# ledstripschematic.net
KiCad netlist of a schematic drawn in EasyEDA
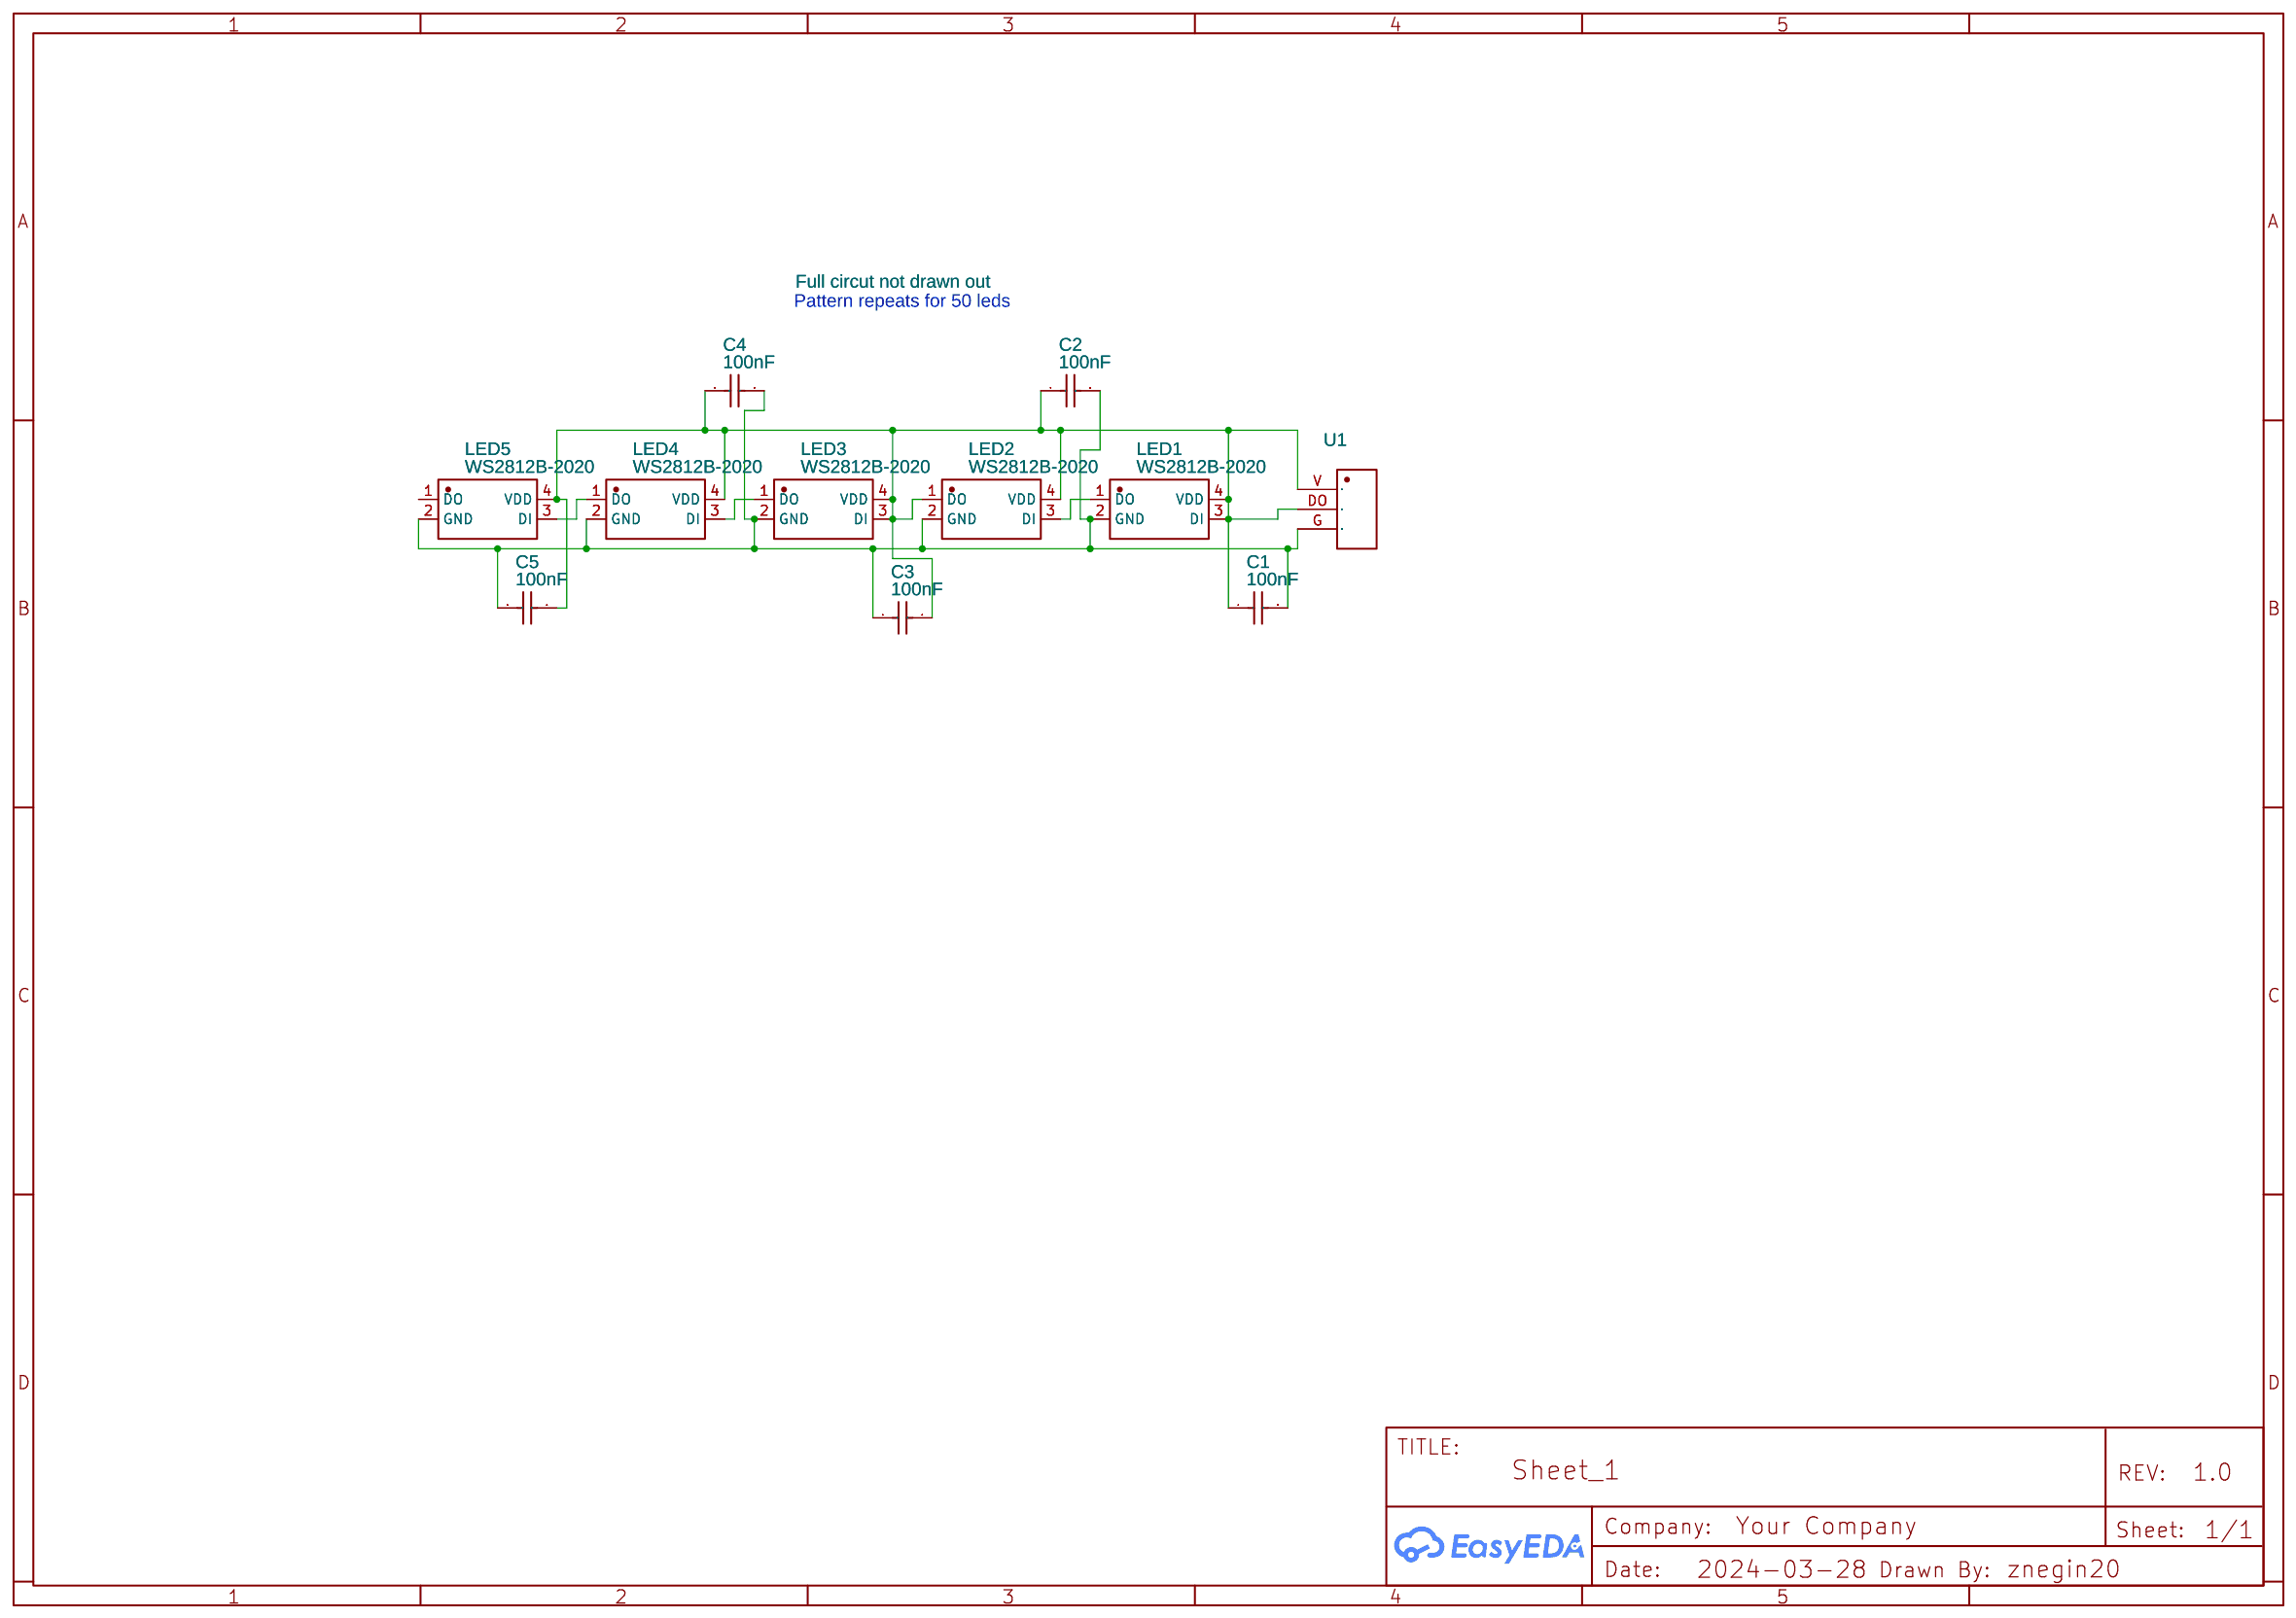
[diagram p0: schematic sheet]

(export (version "E")
  (design (tool "Eeschema 10.0.6"))
  (components
    (comp (ref "C1")
      (value "100nF")
      (fields
        (field (name "Manufacturer Part") "CL05B104KO5NNNC")
        (field (name "Manufacturer") "SAMSUNG(三星)")
      )
      (libsource (lib "") (part "CL05B104KO5NNNC"))
    )
    (comp (ref "C2")
      (value "100nF")
      (fields
        (field (name "Manufacturer Part") "CL05B104KO5NNNC")
        (field (name "Manufacturer") "SAMSUNG(三星)")
      )
      (libsource (lib "") (part "CL05B104KO5NNNC"))
    )
    (comp (ref "C3")
      (value "100nF")
      (fields
        (field (name "Manufacturer Part") "CL05B104KO5NNNC")
        (field (name "Manufacturer") "SAMSUNG(三星)")
      )
      (libsource (lib "") (part "CL05B104KO5NNNC"))
    )
    (comp (ref "C4")
      (value "100nF")
      (fields
        (field (name "Manufacturer Part") "CL05B104KO5NNNC")
        (field (name "Manufacturer") "SAMSUNG(三星)")
      )
      (libsource (lib "") (part "CL05B104KO5NNNC"))
    )
    (comp (ref "C5")
      (value "100nF")
      (fields
        (field (name "Manufacturer Part") "CL05B104KO5NNNC")
        (field (name "Manufacturer") "SAMSUNG(三星)")
      )
      (libsource (lib "") (part "CL05B104KO5NNNC"))
    )
    (comp (ref "LED1")
      (value "WS2812B-2020")
      (fields (field (name "Manufacturer") "worldsemi"))
      (libsource (lib "") (part "WS2812B-2020"))
    )
    (comp (ref "LED2")
      (value "WS2812B-2020")
      (fields (field (name "Manufacturer") "worldsemi"))
      (libsource (lib "") (part "WS2812B-2020"))
    )
    (comp (ref "LED3")
      (value "WS2812B-2020")
      (fields (field (name "Manufacturer") "worldsemi"))
      (libsource (lib "") (part "WS2812B-2020"))
    )
    (comp (ref "LED4")
      (value "WS2812B-2020")
      (fields (field (name "Manufacturer") "worldsemi"))
      (libsource (lib "") (part "WS2812B-2020"))
    )
    (comp (ref "LED5")
      (value "WS2812B-2020")
      (fields (field (name "Manufacturer") "worldsemi"))
      (libsource (lib "") (part "WS2812B-2020"))
    )
    (comp (ref "U1")
      (value "Full circut not drawn out")
      (fields (field (name "Manufacturer Part") "A2-3PA-2.54DSA(71)") (field (name "Manufacturer") "HRS(广濑)"))
      (libsource (lib "") (part "A2-3PA-2.54DSA(71)"))
    )
  )
  (nets
    (net (code "1") (name "Net-(LED1-DI)") (class "Default")
      (node (ref "C1") (pin "1") (pinfunction "1_1") (pintype "input"))
      (node (ref "C2") (pin "1") (pinfunction "1_1") (pintype "input"))
      (node (ref "C3") (pin "2") (pinfunction "2_2") (pintype "input"))
      (node (ref "C4") (pin "1") (pinfunction "1_1") (pintype "input"))
      (node (ref "C5") (pin "2") (pinfunction "2_2") (pintype "input"))
      (node (ref "LED1") (pin "3") (pinfunction "DI_3") (pintype "unspecified"))
      (node (ref "LED1") (pin "4") (pinfunction "VDD_4") (pintype "unspecified"))
      (node (ref "LED2") (pin "1") (pinfunction "DO_1") (pintype "unspecified"))
      (node (ref "LED2") (pin "4") (pinfunction "VDD_4") (pintype "unspecified"))
      (node (ref "LED3") (pin "3") (pinfunction "DI_3") (pintype "unspecified"))
      (node (ref "LED3") (pin "4") (pinfunction "VDD_4") (pintype "unspecified"))
      (node (ref "LED4") (pin "4") (pinfunction "VDD_4") (pintype "unspecified"))
      (node (ref "LED5") (pin "4") (pinfunction "VDD_4") (pintype "unspecified"))
      (node (ref "U1") (pin "DO") (pinfunction "2_DO") (pintype "unspecified"))
      (node (ref "U1") (pin "V") (pinfunction "1_V") (pintype "unspecified"))
    )
    (net (code "2") (name "Net-(LED1-DO)") (class "Default")
      (node (ref "LED1") (pin "1") (pinfunction "DO_1") (pintype "unspecified"))
      (node (ref "LED2") (pin "3") (pinfunction "DI_3") (pintype "unspecified"))
    )
    (net (code "3") (name "Net-(LED1-GND)") (class "Default")
      (node (ref "C1") (pin "2") (pinfunction "2_2") (pintype "input"))
      (node (ref "C2") (pin "2") (pinfunction "2_2") (pintype "input"))
      (node (ref "C3") (pin "1") (pinfunction "1_1") (pintype "input"))
      (node (ref "C4") (pin "2") (pinfunction "2_2") (pintype "input"))
      (node (ref "C5") (pin "1") (pinfunction "1_1") (pintype "input"))
      (node (ref "LED1") (pin "2") (pinfunction "GND_2") (pintype "unspecified"))
      (node (ref "LED2") (pin "2") (pinfunction "GND_2") (pintype "unspecified"))
      (node (ref "LED3") (pin "2") (pinfunction "GND_2") (pintype "unspecified"))
      (node (ref "LED4") (pin "2") (pinfunction "GND_2") (pintype "unspecified"))
      (node (ref "LED5") (pin "2") (pinfunction "GND_2") (pintype "unspecified"))
      (node (ref "U1") (pin "G") (pinfunction "3_G") (pintype "unspecified"))
    )
    (net (code "4") (name "Net-(LED3-DO)") (class "Default")
      (node (ref "LED3") (pin "1") (pinfunction "DO_1") (pintype "unspecified"))
      (node (ref "LED4") (pin "3") (pinfunction "DI_3") (pintype "unspecified"))
    )
    (net (code "5") (name "Net-(LED4-DO)") (class "Default")
      (node (ref "LED4") (pin "1") (pinfunction "DO_1") (pintype "unspecified"))
      (node (ref "LED5") (pin "3") (pinfunction "DI_3") (pintype "unspecified"))
    )
    (net (code "6") (name "unconnected-(LED5-DO-Pad1)") (class "Default")
      (node (ref "LED5") (pin "1") (pinfunction "DO_1") (pintype "unspecified"))
    )
  )
)
